# AMS_Board_schematic.net
KiCad netlist of a schematic drawn in Altium Designer
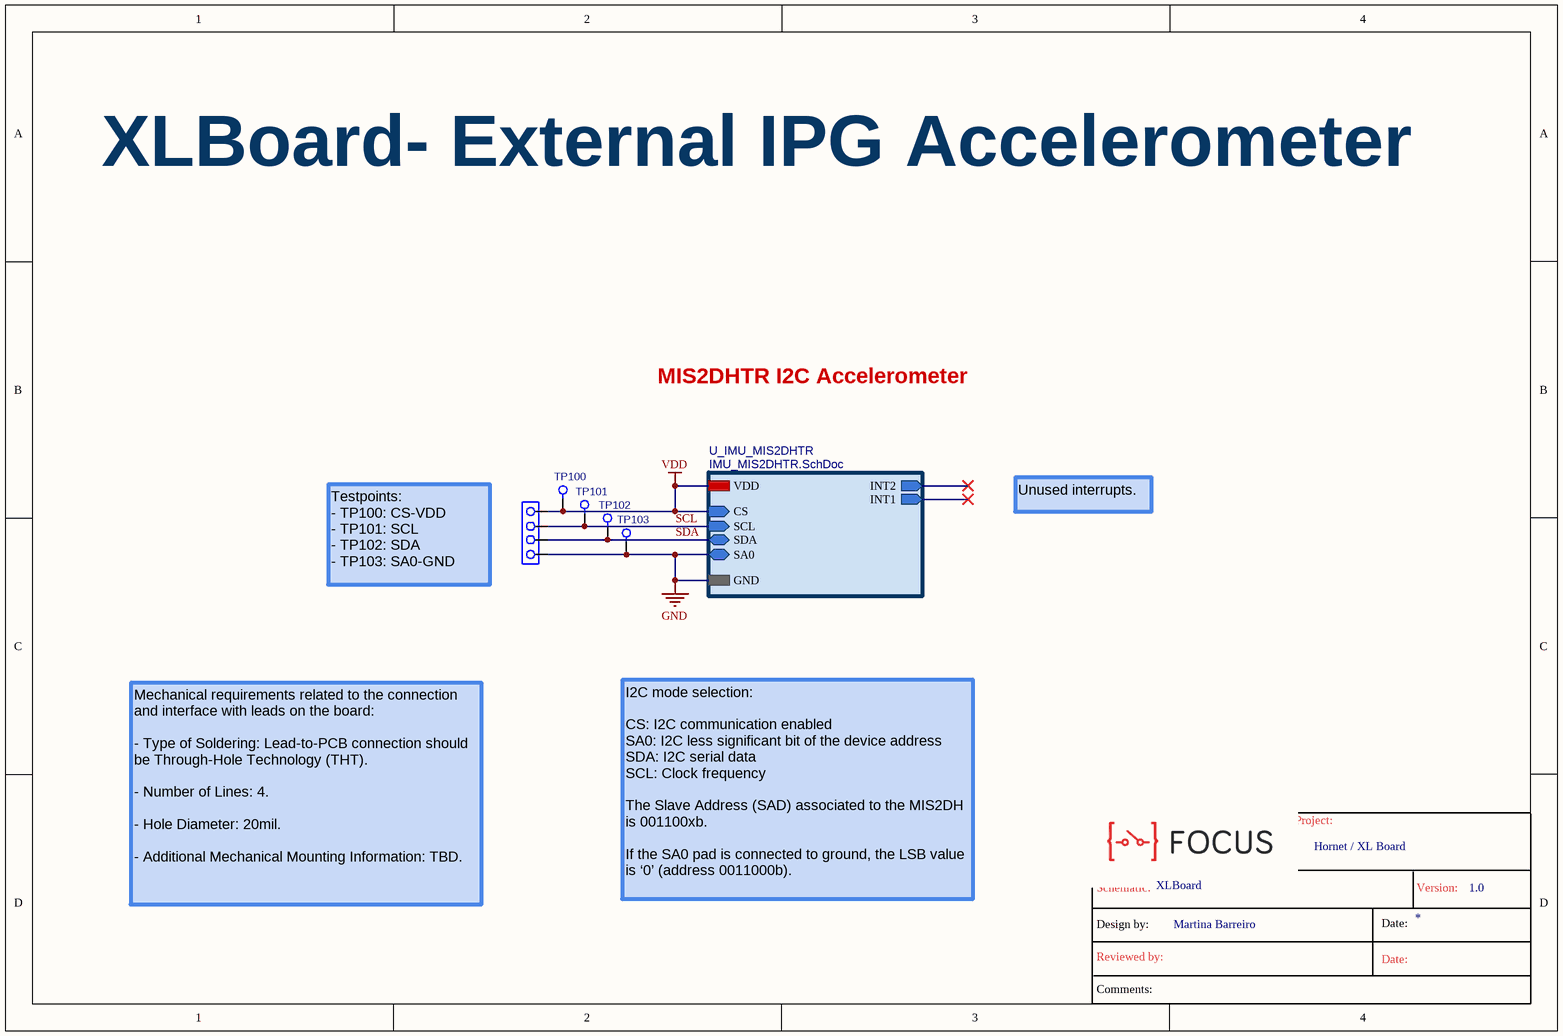
[diagram p0: AMS Board schematic.SchDoc]

(export (version "E")
  (design (tool "Eeschema 10.0.6"))
  (components
    (comp (ref "J100")
      (value "THPAD_20m")
      (footprint "FEEDHOLE_20mil")
      (description "FT pad, Thru-hole, 20 mil hole")
      (libsource (lib "ME-IPG-V1") (part "HOLE_20m"))
    )
    (comp (ref "J101")
      (value "THPAD_20m")
      (footprint "FEEDHOLE_20mil")
      (description "FT pad, Thru-hole, 20 mil hole")
      (libsource (lib "ME-IPG-V1") (part "HOLE_20m"))
    )
    (comp (ref "J102")
      (value "THPAD_20m")
      (footprint "FEEDHOLE_20mil")
      (description "FT pad, Thru-hole, 20 mil hole")
      (libsource (lib "ME-IPG-V1") (part "HOLE_20m"))
    )
    (comp (ref "J103")
      (value "THPAD_20m")
      (footprint "FEEDHOLE_20mil")
      (description "FT pad, Thru-hole, 20 mil hole")
      (libsource (lib "ME-IPG-V1") (part "HOLE_20m"))
    )
    (comp (ref "TP100")
      (value "Test Point")
      (footprint "testpad_0.9mm")
      (description "Test pad, 0.90mm circular pad")
      (libsource (lib "ME-IPG-V1") (part "Test Point"))
    )
    (comp (ref "TP101")
      (value "Test Point")
      (footprint "testpad_0.9mm")
      (description "Test pad, 0.90mm circular pad")
      (libsource (lib "ME-IPG-V1") (part "Test Point"))
    )
    (comp (ref "TP102")
      (value "Test Point")
      (footprint "testpad_0.9mm")
      (description "Test pad, 0.90mm circular pad")
      (libsource (lib "ME-IPG-V1") (part "Test Point"))
    )
    (comp (ref "TP103")
      (value "Test Point")
      (footprint "testpad_0.9mm")
      (description "Test pad, 0.90mm circular pad")
      (libsource (lib "ME-IPG-V1") (part "Test Point"))
    )
  )
  (nets
    (net (code "3") (name "/SCL") (class "Default")
      (node (ref "J101") (pin "1") (pinfunction "1_1") (pintype "passive"))
      (node (ref "TP101") (pin "1") (pinfunction "1_1") (pintype "passive"))
    )
    (net (code "4") (name "/SDA") (class "Default")
      (node (ref "J102") (pin "1") (pinfunction "1_1") (pintype "passive"))
      (node (ref "TP102") (pin "1") (pinfunction "1_1") (pintype "passive"))
    )
    (net (code "5") (name "GND") (class "Default")
      (node (ref "J103") (pin "1") (pinfunction "1_1") (pintype "passive"))
      (node (ref "TP103") (pin "1") (pinfunction "1_1") (pintype "passive"))
    )
    (net (code "6") (name "VDD") (class "Default")
      (node (ref "J100") (pin "1") (pinfunction "1_1") (pintype "passive"))
      (node (ref "TP100") (pin "1") (pinfunction "1_1") (pintype "passive"))
    )
  )
)
